# PWR_RELAY.net
KiCad netlist of a schematic drawn in Altium Designer
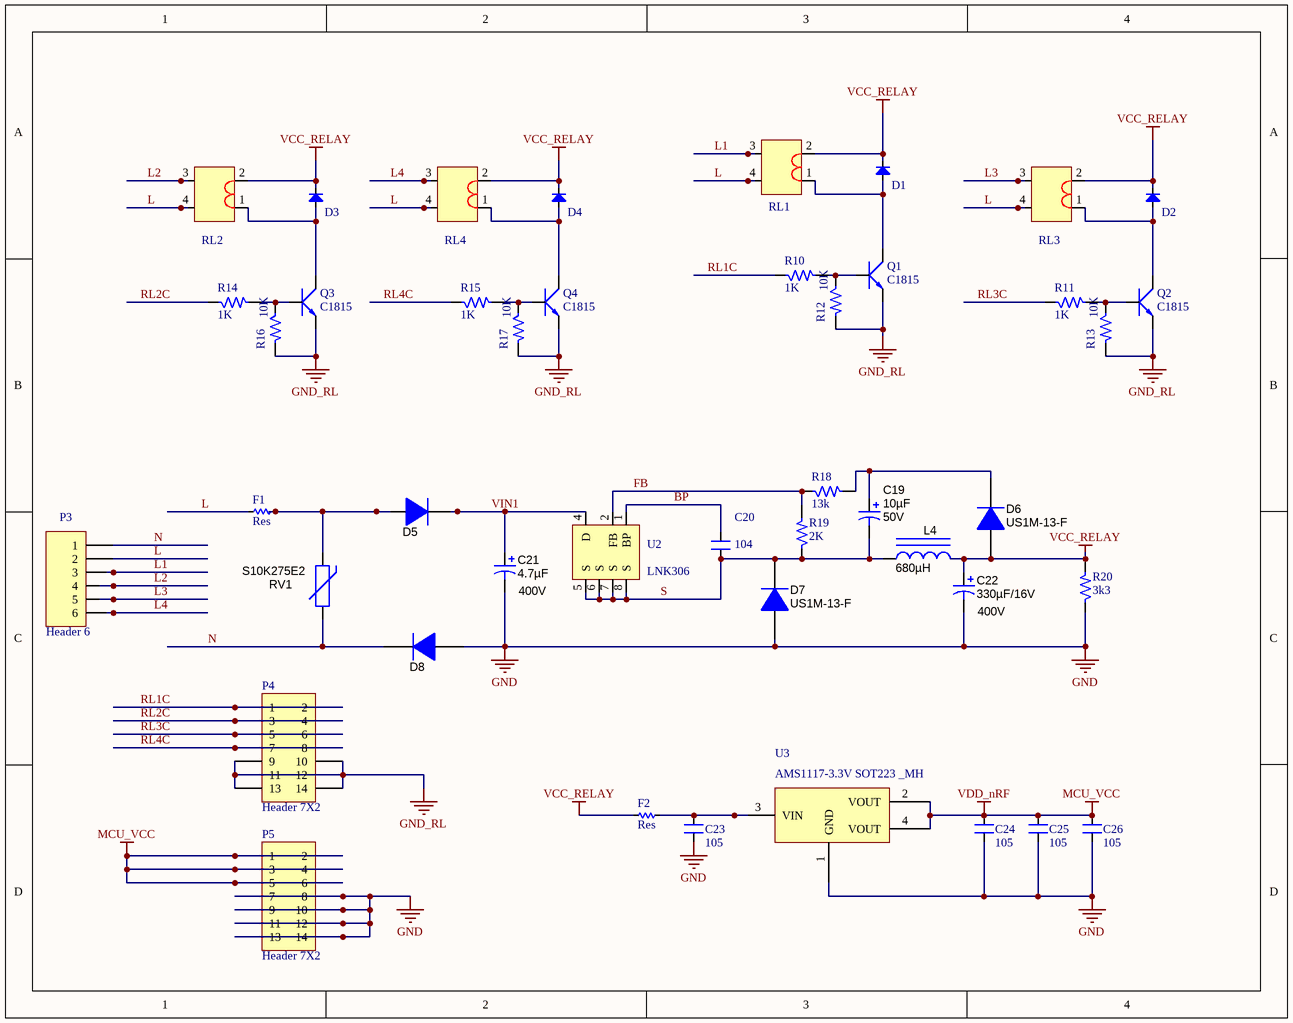
[diagram p0: PWR&RELAY.SchDoc]

(export (version "E")
  (design (tool "Eeschema 10.0.6"))
  (components
    (comp (ref "C19")
      (value "ECA-1HHG100")
      (footprint "PcbLib1:NHG_500x1100")
      (description "CAP, AL, 10 µF, 50 V, +/- 20%, TH")
      (fields
        (field (name "VALUEDISPLAYED") "10µF")
        (field (name "MANUFACTURER") "Panasonic")
        (field (name "VALUE2") "50V")
        (field (name "PUBLISHER") "Texas Instruments")
      )
      (libsource (lib "Capacitor_Aluminum") (part "ECA-1HHG100"))
    )
    (comp (ref "C20")
      (value "104")
      (footprint "0805_HV")
      (description "Cap SMD")
      (libsource (lib "hatcatbietbay") (part "CM"))
    )
    (comp (ref "C21")
      (value "400AX6R8M8x11")
      (footprint "PcbLib1:PANACAP-G-GENERIC")
      (description "CAP, AL, 6.8uF, 400V, +/-20%, TH")
      (fields
        (field (name "VALUEDISPLAYED") "4.7µF")
        (field (name "MANUFACTURER") "Rubycon")
        (field (name "VALUE2") "400V")
        (field (name "PUBLISHER") "Texas Instruments")
      )
      (libsource (lib "Capacitor_Aluminum") (part "400AX6R8M8x11"))
    )
    (comp (ref "C22")
      (value "400AX6R8M8x11")
      (footprint "PcbLib1:CAPPRD350W60D800H1100")
      (description "CAP, AL, 6.8uF, 400V, +/-20%, TH")
      (fields
        (field (name "VALUEDISPLAYED") "330µF/16V")
        (field (name "MANUFACTURER") "Rubycon")
        (field (name "VALUE2") "400V")
        (field (name "PUBLISHER") "Texas Instruments")
      )
      (libsource (lib "Capacitor_Aluminum") (part "400AX6R8M8x11"))
    )
    (comp (ref "C23")
      (value "105")
      (footprint "0805_HV")
      (description "Cap SMD")
      (libsource (lib "hatcatbietbay") (part "CM"))
    )
    (comp (ref "C24")
      (value "105")
      (footprint "0805_HV")
      (description "Cap SMD")
      (libsource (lib "hatcatbietbay") (part "CM"))
    )
    (comp (ref "C25")
      (value "105")
      (footprint "0805_HV")
      (description "Cap SMD")
      (libsource (lib "hatcatbietbay") (part "CM"))
    )
    (comp (ref "C26")
      (value "105")
      (footprint "0805_HV")
      (description "Cap SMD")
      (libsource (lib "hatcatbietbay") (part "CM"))
    )
    (comp (ref "D1")
      (value "Diode SMD")
      (footprint "DIO-SMD-123")
      (description "Default Diode")
      (fields (field (name "PUBLISHER") "Altium Limited"))
      (libsource (lib "LIBRARY") (part "Diode SMD"))
    )
    (comp (ref "D2")
      (value "Diode SMD")
      (footprint "DIO-SMD-123")
      (description "Default Diode")
      (fields (field (name "PUBLISHER") "Altium Limited"))
      (libsource (lib "LIBRARY") (part "Diode SMD"))
    )
    (comp (ref "D3")
      (value "Diode SMD")
      (footprint "DIO-SMD-123")
      (description "Default Diode")
      (fields (field (name "PUBLISHER") "Altium Limited"))
      (libsource (lib "LIBRARY") (part "Diode SMD"))
    )
    (comp (ref "D4")
      (value "Diode SMD")
      (footprint "DIO-SMD-123")
      (description "Default Diode")
      (fields (field (name "PUBLISHER") "Altium Limited"))
      (libsource (lib "LIBRARY") (part "Diode SMD"))
    )
    (comp (ref "D5")
      (value "US1M-13-F")
      (footprint "PcbLib1:SMB")
      (description "Diode, Ultrafast, 600V, 1A, SMB")
      (fields (field (name "MANUFACTURER") "Diodes Inc.") (field (name "PUBLISHER") "Texas Instruments"))
      (libsource (lib "Diode") (part "MURS160-13-F"))
    )
    (comp (ref "D6")
      (value "US1M-13-F")
      (footprint "PcbLib1:SMB")
      (description "Diode, Ultrafast, 600V, 1A, SMB")
      (fields
        (field (name "PARTNUMBER") "US1M-13-F")
        (field (name "MANUFACTURER") "Diodes Inc.")
        (field (name "PUBLISHER") "Texas Instruments")
      )
      (libsource (lib "Diode") (part "MURS160-13-F"))
    )
    (comp (ref "D7")
      (value "US1M-13-F")
      (footprint "PcbLib1:SMB")
      (description "Diode, Ultrafast, 600V, 1A, SMB")
      (fields
        (field (name "PARTNUMBER") "US1M-13-F")
        (field (name "MANUFACTURER") "Diodes Inc.")
        (field (name "PUBLISHER") "Texas Instruments")
      )
      (libsource (lib "Diode") (part "MURS160-13-F"))
    )
    (comp (ref "D8")
      (value "US1M-13-F")
      (footprint "PcbLib1:SMB")
      (description "Diode, Ultrafast, 600V, 1A, SMB")
      (fields (field (name "MANUFACTURER") "Diodes Inc.") (field (name "PUBLISHER") "Texas Instruments"))
      (libsource (lib "Diode") (part "MURS160-13-F"))
    )
    (comp (ref "F1")
      (value "Res")
      (footprint "1206")
      (description "Resistor")
      (fields
        (field (name "MANUFACTURER") "Generic Components")
        (field (name "PUBLISHER") "Altium Hobart Technology Centre")
      )
      (libsource (lib "LIBRARY") (part "Res-SMD"))
    )
    (comp (ref "F2")
      (value "Res")
      (footprint "1206")
      (description "Resistor")
      (fields
        (field (name "MANUFACTURER") "Generic Components")
        (field (name "PUBLISHER") "Altium Hobart Technology Centre")
      )
      (libsource (lib "LIBRARY") (part "Res-SMD"))
    )
    (comp (ref "L4")
      (value "7447480331")
      (footprint "PcbLib1:IND_WE-TI_8095")
      (description "Inductor, Wirewound, Ferrite, 330 µH, 1.4 A, 0.3 ohm, TH")
      (fields
        (field (name "VALUEDISPLAYED") "680µH")
        (field (name "MANUFACTURER") "Wurth Elektronik")
        (field (name "PUBLISHER") "Texas Instruments")
      )
      (libsource (lib "Inductor_Wurth") (part "7447480331"))
    )
    (comp (ref "P3")
      (value "Header 6")
      (footprint "CONWALL_SWITH-4")
      (description "Header, 6-Pin")
      (fields (field (name "PUBLISHER") "Altium Limited"))
      (libsource (lib "Miscellaneous Connectors") (part "Header 6"))
    )
    (comp (ref "P4")
      (value "Header 7X2")
      (footprint "CON14_1.27")
      (description "Header, 7-Pin, Dual row")
      (fields (field (name "PUBLISHER") "Altium Limited"))
      (libsource (lib "Miscellaneous Connectors") (part "Header 7X2"))
    )
    (comp (ref "P5")
      (value "Header 7X2")
      (footprint "CON14_1.27")
      (description "Header, 7-Pin, Dual row")
      (fields (field (name "PUBLISHER") "Altium Limited"))
      (libsource (lib "Miscellaneous Connectors") (part "Header 7X2"))
    )
    (comp (ref "Q1")
      (value "C1815")
      (footprint "SOT23B")
      (description "NPN 600mW, ECB")
      (libsource (lib "hatcatbietbay") (part "C1815"))
    )
    (comp (ref "Q2")
      (value "C1815")
      (footprint "SOT23B")
      (description "NPN 600mW, ECB")
      (libsource (lib "hatcatbietbay") (part "C1815"))
    )
    (comp (ref "Q3")
      (value "C1815")
      (footprint "SOT23B")
      (description "NPN 600mW, ECB")
      (libsource (lib "hatcatbietbay") (part "C1815"))
    )
    (comp (ref "Q4")
      (value "C1815")
      (footprint "SOT23B")
      (description "NPN 600mW, ECB")
      (libsource (lib "hatcatbietbay") (part "C1815"))
    )
    (comp (ref "R10")
      (value "1K")
      (footprint "PcbLib1:0603")
      (description "Resistor 1/4W")
      (libsource (lib "hatcatbietbay") (part "R"))
    )
    (comp (ref "R11")
      (value "1K")
      (footprint "PcbLib1:0603")
      (description "Resistor 1/4W")
      (libsource (lib "hatcatbietbay") (part "R"))
    )
    (comp (ref "R12")
      (value "10K")
      (footprint "PcbLib1:0603")
      (description "Resistor 1/4W")
      (libsource (lib "hatcatbietbay") (part "R"))
    )
    (comp (ref "R13")
      (value "10K")
      (footprint "PcbLib1:0603")
      (description "Resistor 1/4W")
      (libsource (lib "hatcatbietbay") (part "R"))
    )
    (comp (ref "R14")
      (value "1K")
      (footprint "PcbLib1:0603")
      (description "Resistor 1/4W")
      (libsource (lib "hatcatbietbay") (part "R"))
    )
    (comp (ref "R15")
      (value "1K")
      (footprint "PcbLib1:0603")
      (description "Resistor 1/4W")
      (libsource (lib "hatcatbietbay") (part "R"))
    )
    (comp (ref "R16")
      (value "10K")
      (footprint "PcbLib1:0603")
      (description "Resistor 1/4W")
      (libsource (lib "hatcatbietbay") (part "R"))
    )
    (comp (ref "R17")
      (value "10K")
      (footprint "PcbLib1:0603")
      (description "Resistor 1/4W")
      (libsource (lib "hatcatbietbay") (part "R"))
    )
    (comp (ref "R18")
      (value "13k")
      (footprint "0805_HV")
      (description "Resistor 1/4W")
      (libsource (lib "hatcatbietbay") (part "R"))
    )
    (comp (ref "R19")
      (value "2K")
      (footprint "0805_HV")
      (description "Resistor 1/4W")
      (libsource (lib "hatcatbietbay") (part "R"))
    )
    (comp (ref "R20")
      (value "3k3")
      (footprint "0805_HV")
      (description "Resistor 1/4W")
      (libsource (lib "hatcatbietbay") (part "R"))
    )
    (comp (ref "RL1")
      (value "Component_1")
      (footprint "AZ7705")
      (libsource (lib "Zettler") (part "Component_1"))
    )
    (comp (ref "RL2")
      (value "Component_1")
      (footprint "AZ7705")
      (libsource (lib "Zettler") (part "Component_1"))
    )
    (comp (ref "RL3")
      (value "Component_1")
      (footprint "AZ7705")
      (libsource (lib "Zettler") (part "Component_1"))
    )
    (comp (ref "RL4")
      (value "Component_1")
      (footprint "AZ7705")
      (libsource (lib "Zettler") (part "Component_1"))
    )
    (comp (ref "RV1")
      (value "S10K275E2")
      (footprint "PcbLib1:VAR_S10K275E2")
      (description "Varistor 275V RMS 10MM Radial, TH")
      (fields
        (field (name "MANUFACTURER") "EPCOS Inc")
        (field (name "SYMBOLCREATOR") "a0412235")
        (field (name "PUBLISHER") "Texas Instruments")
      )
      (libsource (lib "Other_Passive") (part "S10K275E2"))
    )
    (comp (ref "U2") (value "LNK306") (footprint "SOP 7") (libsource (lib "LNK304") (part "Component_1")))
    (comp (ref "U3")
      (value "AMS1117-3.3V SOT223 _MH")
      (footprint "SOT223")
      (libsource (lib "MH_DA_THU_VIEN_16122016") (part "AMS1117-3.3V SOT223 _MH"))
    )
  )
  (nets
    (net (code "1") (name "/BP") (class "Default")
      (node (ref "C20") (pin "2") (pinfunction "2_2") (pintype "passive"))
      (node (ref "U2") (pin "1") (pinfunction "BP_1") (pintype "passive"))
    )
    (net (code "2") (name "/FB") (class "Default")
      (node (ref "R18") (pin "1") (pinfunction "1_1") (pintype "passive"))
      (node (ref "R19") (pin "2") (pinfunction "2_2") (pintype "passive"))
      (node (ref "U2") (pin "2") (pinfunction "FB_2") (pintype "passive"))
    )
    (net (code "3") (name "/L") (class "Default")
      (node (ref "F1") (pin "2") (pinfunction "2_2") (pintype "passive"))
      (node (ref "P3") (pin "2") (pinfunction "2_2") (pintype "passive"))
      (node (ref "RL1") (pin "4") (pintype "passive"))
      (node (ref "RL2") (pin "4") (pintype "passive"))
      (node (ref "RL3") (pin "4") (pintype "passive"))
      (node (ref "RL4") (pin "4") (pintype "passive"))
    )
    (net (code "4") (name "/L1") (class "Default")
      (node (ref "P3") (pin "3") (pinfunction "3_3") (pintype "passive"))
      (node (ref "RL1") (pin "3") (pintype "passive"))
    )
    (net (code "5") (name "/L2") (class "Default")
      (node (ref "P3") (pin "4") (pinfunction "4_4") (pintype "passive"))
      (node (ref "RL2") (pin "3") (pintype "passive"))
    )
    (net (code "6") (name "/L3") (class "Default")
      (node (ref "P3") (pin "5") (pinfunction "5_5") (pintype "passive"))
      (node (ref "RL3") (pin "3") (pintype "passive"))
    )
    (net (code "7") (name "/L4") (class "Default")
      (node (ref "P3") (pin "6") (pinfunction "6_6") (pintype "passive"))
      (node (ref "RL4") (pin "3") (pintype "passive"))
    )
    (net (code "8") (name "/N") (class "Default")
      (node (ref "D8") (pin "1") (pinfunction "K_1") (pintype "passive"))
      (node (ref "P3") (pin "1") (pinfunction "1_1") (pintype "passive"))
      (node (ref "RV1") (pin "1") (pinfunction "1_1") (pintype "passive"))
    )
    (net (code "9") (name "/RL1C") (class "Default")
      (node (ref "P4") (pin "1") (pinfunction "1_1") (pintype "passive"))
      (node (ref "P4") (pin "2") (pinfunction "2_2") (pintype "passive"))
      (node (ref "R10") (pin "1") (pinfunction "1_1") (pintype "passive"))
    )
    (net (code "10") (name "/RL2C") (class "Default")
      (node (ref "P4") (pin "3") (pinfunction "3_3") (pintype "passive"))
      (node (ref "P4") (pin "4") (pinfunction "4_4") (pintype "passive"))
      (node (ref "R14") (pin "1") (pinfunction "1_1") (pintype "passive"))
    )
    (net (code "11") (name "/RL3C") (class "Default")
      (node (ref "P4") (pin "5") (pinfunction "5_5") (pintype "passive"))
      (node (ref "P4") (pin "6") (pinfunction "6_6") (pintype "passive"))
      (node (ref "R11") (pin "1") (pinfunction "1_1") (pintype "passive"))
    )
    (net (code "12") (name "/RL4C") (class "Default")
      (node (ref "P4") (pin "7") (pinfunction "7_7") (pintype "passive"))
      (node (ref "P4") (pin "8") (pinfunction "8_8") (pintype "passive"))
      (node (ref "R15") (pin "1") (pinfunction "1_1") (pintype "passive"))
    )
    (net (code "13") (name "/S") (class "Default")
      (node (ref "C19") (pin "2") (pinfunction "-_2") (pintype "passive"))
      (node (ref "C20") (pin "1") (pinfunction "1_1") (pintype "passive"))
      (node (ref "D7") (pin "1") (pinfunction "K_1") (pintype "passive"))
      (node (ref "L4") (pin "1") (pinfunction "1_1") (pintype "passive"))
      (node (ref "R19") (pin "1") (pinfunction "1_1") (pintype "passive"))
      (node (ref "U2") (pin "5") (pinfunction "S_5") (pintype "passive"))
      (node (ref "U2") (pin "6") (pinfunction "S_6") (pintype "passive"))
      (node (ref "U2") (pin "7") (pinfunction "S_7") (pintype "passive"))
      (node (ref "U2") (pin "8") (pinfunction "S_8") (pintype "passive"))
    )
    (net (code "14") (name "/VIN1") (class "Default")
      (node (ref "C21") (pin "1") (pinfunction "+_1") (pintype "passive"))
      (node (ref "D5") (pin "1") (pinfunction "K_1") (pintype "passive"))
      (node (ref "U2") (pin "4") (pinfunction "D_4") (pintype "passive"))
    )
    (net (code "15") (name "GND") (class "Default")
      (node (ref "C21") (pin "2") (pinfunction "-_2") (pintype "passive"))
      (node (ref "C22") (pin "2") (pinfunction "-_2") (pintype "passive"))
      (node (ref "C23") (pin "1") (pinfunction "1_1") (pintype "passive"))
      (node (ref "C24") (pin "1") (pinfunction "1_1") (pintype "passive"))
      (node (ref "C25") (pin "1") (pinfunction "1_1") (pintype "passive"))
      (node (ref "C26") (pin "1") (pinfunction "1_1") (pintype "passive"))
      (node (ref "D7") (pin "2") (pinfunction "A_2") (pintype "passive"))
      (node (ref "D8") (pin "2") (pinfunction "A_2") (pintype "passive"))
      (node (ref "P5") (pin "10") (pinfunction "10_10") (pintype "passive"))
      (node (ref "P5") (pin "11") (pinfunction "11_11") (pintype "passive"))
      (node (ref "P5") (pin "12") (pinfunction "12_12") (pintype "passive"))
      (node (ref "P5") (pin "13") (pinfunction "13_13") (pintype "passive"))
      (node (ref "P5") (pin "14") (pinfunction "14_14") (pintype "passive"))
      (node (ref "P5") (pin "7") (pinfunction "7_7") (pintype "passive"))
      (node (ref "P5") (pin "8") (pinfunction "8_8") (pintype "passive"))
      (node (ref "P5") (pin "9") (pinfunction "9_9") (pintype "passive"))
      (node (ref "R20") (pin "1") (pinfunction "1_1") (pintype "passive"))
      (node (ref "U3") (pin "1") (pinfunction "GND_1") (pintype "passive"))
    )
    (net (code "16") (name "GND_RL") (class "Default")
      (node (ref "P4") (pin "10") (pinfunction "10_10") (pintype "passive"))
      (node (ref "P4") (pin "11") (pinfunction "11_11") (pintype "passive"))
      (node (ref "P4") (pin "12") (pinfunction "12_12") (pintype "passive"))
      (node (ref "P4") (pin "13") (pinfunction "13_13") (pintype "passive"))
      (node (ref "P4") (pin "14") (pinfunction "14_14") (pintype "passive"))
      (node (ref "P4") (pin "9") (pinfunction "9_9") (pintype "passive"))
      (node (ref "Q1") (pin "3") (pinfunction "E_3") (pintype "passive"))
      (node (ref "Q2") (pin "3") (pinfunction "E_3") (pintype "passive"))
      (node (ref "Q3") (pin "3") (pinfunction "E_3") (pintype "passive"))
      (node (ref "Q4") (pin "3") (pinfunction "E_3") (pintype "passive"))
      (node (ref "R12") (pin "2") (pinfunction "2_2") (pintype "passive"))
      (node (ref "R13") (pin "2") (pinfunction "2_2") (pintype "passive"))
      (node (ref "R16") (pin "2") (pinfunction "2_2") (pintype "passive"))
      (node (ref "R17") (pin "2") (pinfunction "2_2") (pintype "passive"))
    )
    (net (code "17") (name "MCU_VCC") (class "Default")
      (node (ref "C24") (pin "2") (pinfunction "2_2") (pintype "passive"))
      (node (ref "C25") (pin "2") (pinfunction "2_2") (pintype "passive"))
      (node (ref "C26") (pin "2") (pinfunction "2_2") (pintype "passive"))
      (node (ref "P5") (pin "1") (pinfunction "1_1") (pintype "passive"))
      (node (ref "P5") (pin "2") (pinfunction "2_2") (pintype "passive"))
      (node (ref "P5") (pin "3") (pinfunction "3_3") (pintype "passive"))
      (node (ref "P5") (pin "4") (pinfunction "4_4") (pintype "passive"))
      (node (ref "P5") (pin "5") (pinfunction "5_5") (pintype "passive"))
      (node (ref "P5") (pin "6") (pinfunction "6_6") (pintype "passive"))
      (node (ref "U3") (pin "2") (pinfunction "VOUT_2") (pintype "passive"))
      (node (ref "U3") (pin "4") (pinfunction "VOUT_4") (pintype "passive"))
    )
    (net (code "18") (name "Net-(C19-+)") (class "Default")
      (node (ref "C19") (pin "1") (pinfunction "+_1") (pintype "passive"))
      (node (ref "D6") (pin "1") (pinfunction "K_1") (pintype "passive"))
      (node (ref "R18") (pin "2") (pinfunction "2_2") (pintype "passive"))
    )
    (net (code "19") (name "Net-(D1-A)") (class "Default")
      (node (ref "D1") (pin "1") (pinfunction "A_1") (pintype "passive"))
      (node (ref "Q1") (pin "2") (pinfunction "C_2") (pintype "passive"))
      (node (ref "RL1") (pin "1") (pintype "passive"))
    )
    (net (code "20") (name "Net-(D2-A)") (class "Default")
      (node (ref "D2") (pin "1") (pinfunction "A_1") (pintype "passive"))
      (node (ref "Q2") (pin "2") (pinfunction "C_2") (pintype "passive"))
      (node (ref "RL3") (pin "1") (pintype "passive"))
    )
    (net (code "21") (name "Net-(D3-A)") (class "Default")
      (node (ref "D3") (pin "1") (pinfunction "A_1") (pintype "passive"))
      (node (ref "Q3") (pin "2") (pinfunction "C_2") (pintype "passive"))
      (node (ref "RL2") (pin "1") (pintype "passive"))
    )
    (net (code "22") (name "Net-(D4-A)") (class "Default")
      (node (ref "D4") (pin "1") (pinfunction "A_1") (pintype "passive"))
      (node (ref "Q4") (pin "2") (pinfunction "C_2") (pintype "passive"))
      (node (ref "RL4") (pin "1") (pintype "passive"))
    )
    (net (code "23") (name "Net-(D5-A)") (class "Default")
      (node (ref "D5") (pin "2") (pinfunction "A_2") (pintype "passive"))
      (node (ref "F1") (pin "1") (pinfunction "1_1") (pintype "passive"))
      (node (ref "RV1") (pin "2") (pinfunction "2_2") (pintype "passive"))
    )
    (net (code "24") (name "Net-(Q1-B)") (class "Default")
      (node (ref "Q1") (pin "1") (pinfunction "B_1") (pintype "passive"))
      (node (ref "R10") (pin "2") (pinfunction "2_2") (pintype "passive"))
      (node (ref "R12") (pin "1") (pinfunction "1_1") (pintype "passive"))
    )
    (net (code "25") (name "Net-(Q2-B)") (class "Default")
      (node (ref "Q2") (pin "1") (pinfunction "B_1") (pintype "passive"))
      (node (ref "R11") (pin "2") (pinfunction "2_2") (pintype "passive"))
      (node (ref "R13") (pin "1") (pinfunction "1_1") (pintype "passive"))
    )
    (net (code "26") (name "Net-(Q3-B)") (class "Default")
      (node (ref "Q3") (pin "1") (pinfunction "B_1") (pintype "passive"))
      (node (ref "R14") (pin "2") (pinfunction "2_2") (pintype "passive"))
      (node (ref "R16") (pin "1") (pinfunction "1_1") (pintype "passive"))
    )
    (net (code "27") (name "Net-(Q4-B)") (class "Default")
      (node (ref "Q4") (pin "1") (pinfunction "B_1") (pintype "passive"))
      (node (ref "R15") (pin "2") (pinfunction "2_2") (pintype "passive"))
      (node (ref "R17") (pin "1") (pinfunction "1_1") (pintype "passive"))
    )
    (net (code "28") (name "Net-(U3-VIN)") (class "Default")
      (node (ref "C23") (pin "2") (pinfunction "2_2") (pintype "passive"))
      (node (ref "F2") (pin "1") (pinfunction "1_1") (pintype "passive"))
      (node (ref "U3") (pin "3") (pinfunction "VIN_3") (pintype "passive"))
    )
    (net (code "29") (name "VCC_RELAY") (class "Default")
      (node (ref "C22") (pin "1") (pinfunction "+_1") (pintype "passive"))
      (node (ref "D1") (pin "2") (pinfunction "K_2") (pintype "passive"))
      (node (ref "D2") (pin "2") (pinfunction "K_2") (pintype "passive"))
      (node (ref "D3") (pin "2") (pinfunction "K_2") (pintype "passive"))
      (node (ref "D4") (pin "2") (pinfunction "K_2") (pintype "passive"))
      (node (ref "D6") (pin "2") (pinfunction "A_2") (pintype "passive"))
      (node (ref "F2") (pin "2") (pinfunction "2_2") (pintype "passive"))
      (node (ref "L4") (pin "2") (pinfunction "2_2") (pintype "passive"))
      (node (ref "R20") (pin "2") (pinfunction "2_2") (pintype "passive"))
      (node (ref "RL1") (pin "2") (pintype "passive"))
      (node (ref "RL2") (pin "2") (pintype "passive"))
      (node (ref "RL3") (pin "2") (pintype "passive"))
      (node (ref "RL4") (pin "2") (pintype "passive"))
    )
  )
)
